# Sheet1.net
KiCad netlist of a schematic drawn in Altium Designer
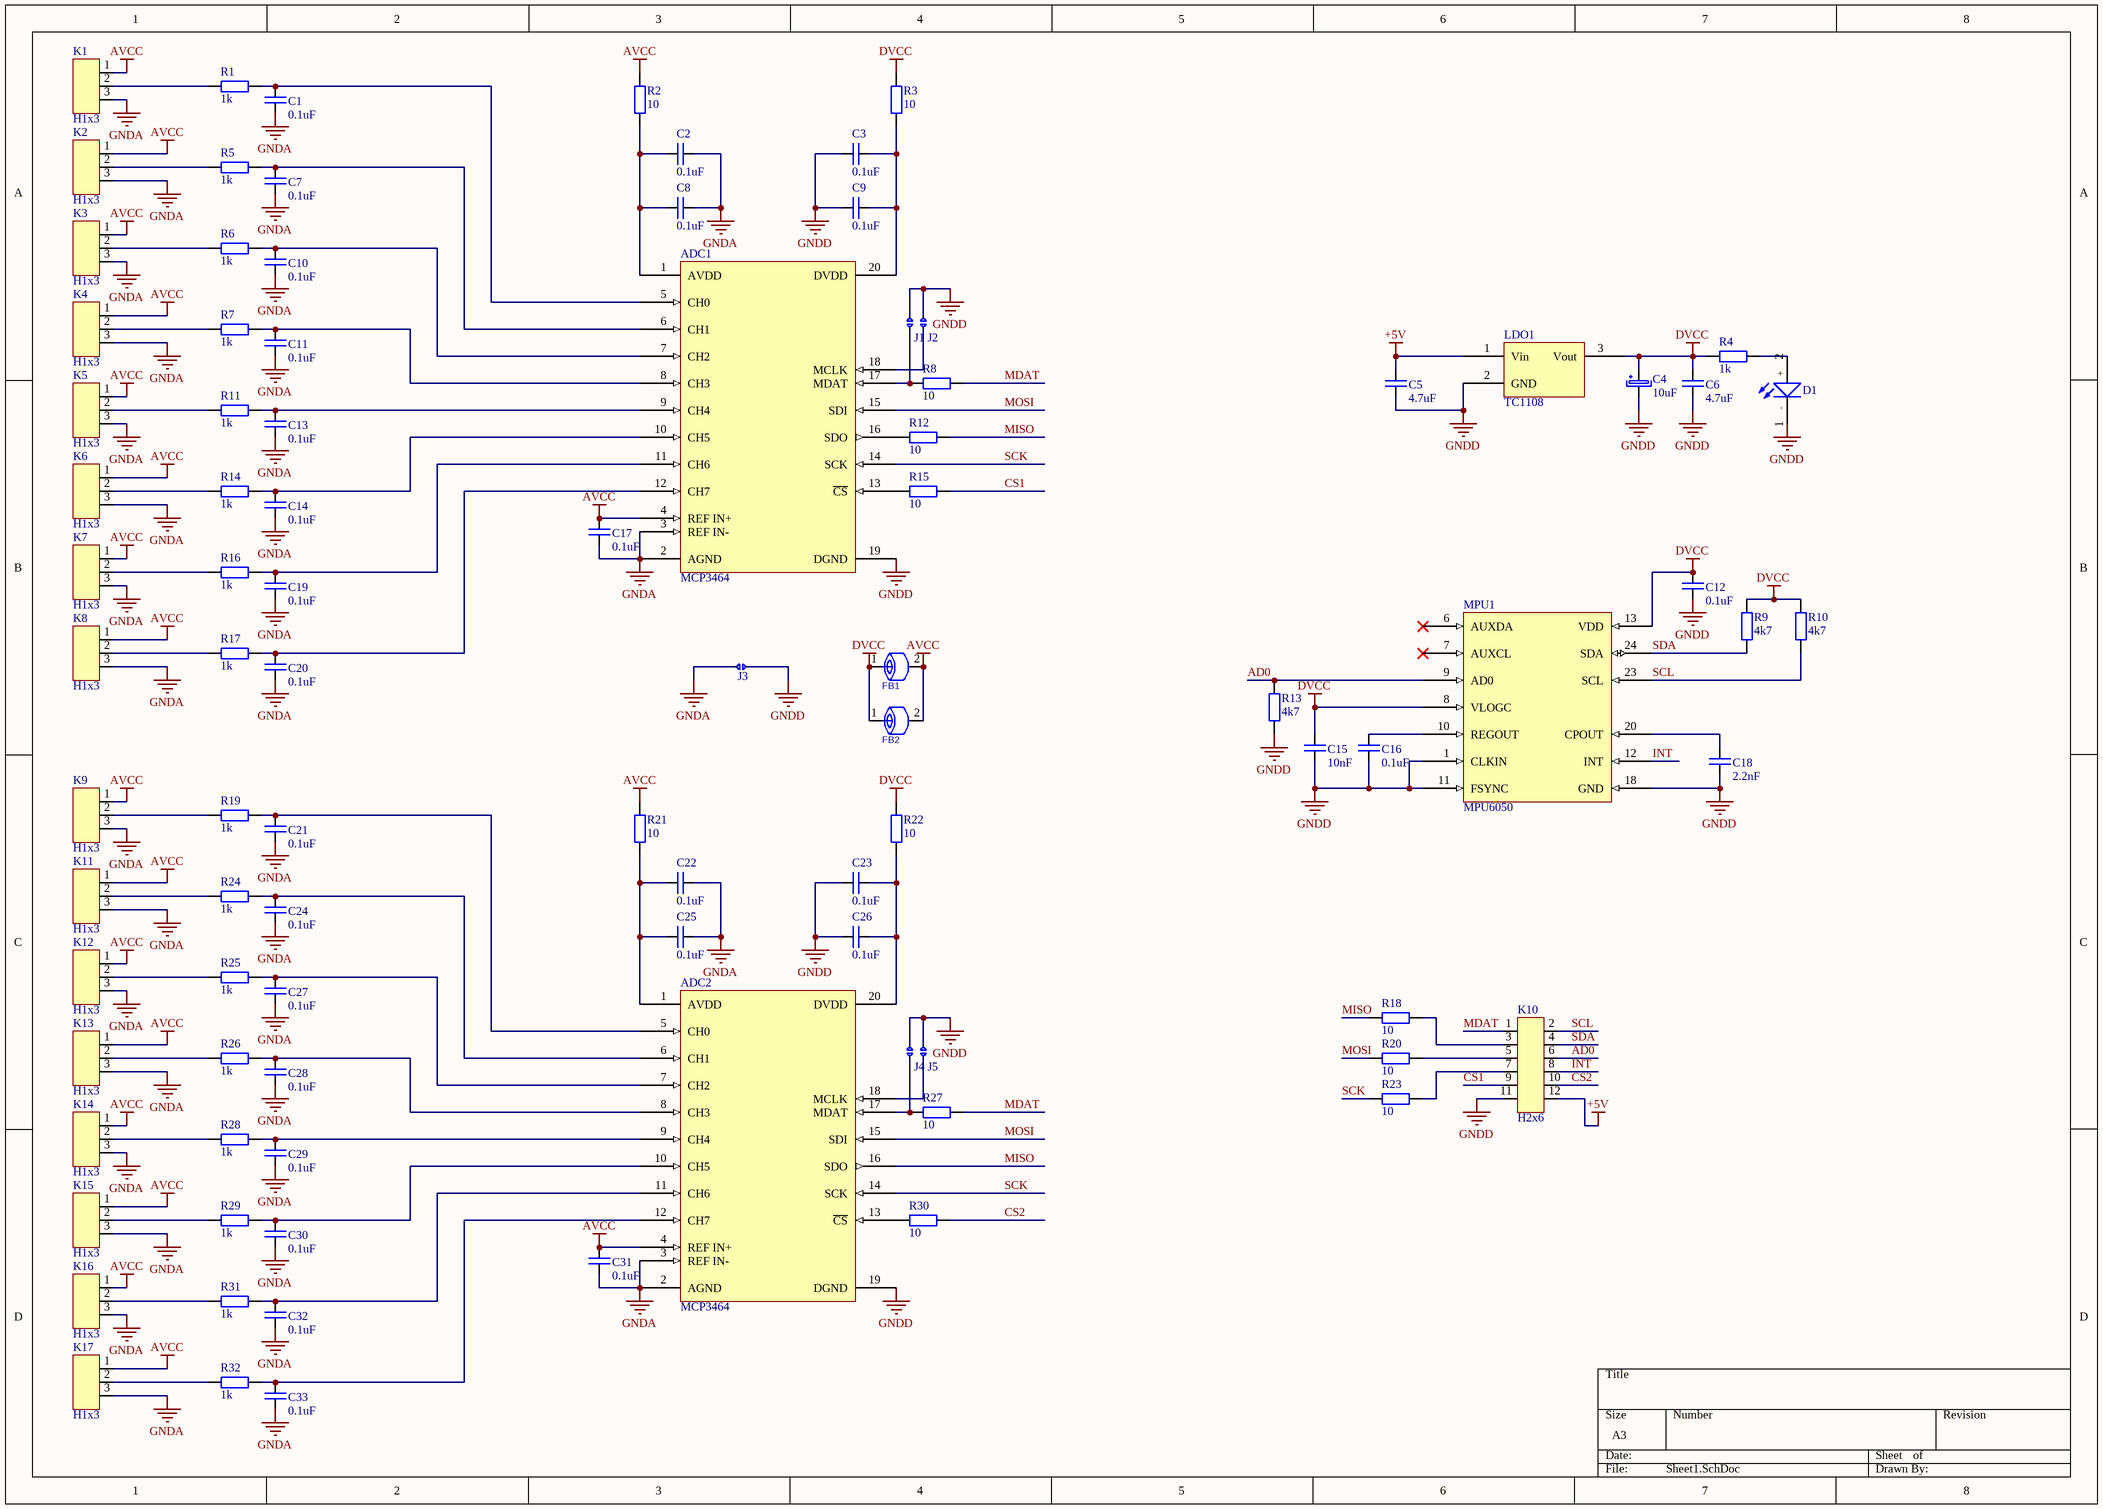
[diagram p0: Sheet1.SchDoc]

(export (version "E")
  (design (tool "Eeschema 10.0.6"))
  (components
    (comp (ref "ADC1")
      (value "MCP3464")
      (footprint "TSOP65P640X120-20N ADC")
      (libsource (lib "IntLibARMA") (part "MCP3464"))
    )
    (comp (ref "ADC2")
      (value "MCP3464")
      (footprint "TSOP65P640X120-20N ADC")
      (libsource (lib "IntLibARMA") (part "MCP3464"))
    )
    (comp (ref "C1")
      (value "0.1uF")
      (footprint "C1608_0603I_M")
      (description "Capacitor")
      (libsource (lib "General") (part "C"))
    )
    (comp (ref "C2")
      (value "0.1uF")
      (footprint "C1608_0603I_M")
      (description "Capacitor")
      (libsource (lib "General") (part "C"))
    )
    (comp (ref "C3")
      (value "0.1uF")
      (footprint "C1608_0603I_M")
      (description "Capacitor")
      (libsource (lib "General") (part "C"))
    )
    (comp (ref "C4")
      (value "10uF")
      (footprint "C Tantal A")
      (description "Capacitor Polarized")
      (libsource (lib "General") (part "C+"))
    )
    (comp (ref "C5")
      (value "4.7uF")
      (footprint "C1608_0603I_M")
      (description "Capacitor")
      (libsource (lib "General") (part "C"))
    )
    (comp (ref "C6")
      (value "4.7uF")
      (footprint "C1608_0603I_M")
      (description "Capacitor")
      (libsource (lib "General") (part "C"))
    )
    (comp (ref "C7")
      (value "0.1uF")
      (footprint "C1608_0603I_M")
      (description "Capacitor")
      (libsource (lib "General") (part "C"))
    )
    (comp (ref "C8")
      (value "0.1uF")
      (footprint "C1608_0603I_M")
      (description "Capacitor")
      (libsource (lib "General") (part "C"))
    )
    (comp (ref "C9")
      (value "0.1uF")
      (footprint "C1608_0603I_M")
      (description "Capacitor")
      (libsource (lib "General") (part "C"))
    )
    (comp (ref "C10")
      (value "0.1uF")
      (footprint "C1608_0603I_M")
      (description "Capacitor")
      (libsource (lib "General") (part "C"))
    )
    (comp (ref "C11")
      (value "0.1uF")
      (footprint "C1608_0603I_M")
      (description "Capacitor")
      (libsource (lib "General") (part "C"))
    )
    (comp (ref "C12")
      (value "0.1uF")
      (footprint "C1608_0603I_M")
      (description "Capacitor")
      (libsource (lib "General") (part "C"))
    )
    (comp (ref "C13")
      (value "0.1uF")
      (footprint "C1608_0603I_M")
      (description "Capacitor")
      (libsource (lib "General") (part "C"))
    )
    (comp (ref "C14")
      (value "0.1uF")
      (footprint "C1608_0603I_M")
      (description "Capacitor")
      (libsource (lib "General") (part "C"))
    )
    (comp (ref "C15")
      (value "10nF")
      (footprint "C1608_0603I_M")
      (description "Capacitor")
      (libsource (lib "General") (part "C"))
    )
    (comp (ref "C16")
      (value "0.1uF")
      (footprint "C1608_0603I_M")
      (description "Capacitor")
      (libsource (lib "General") (part "C"))
    )
    (comp (ref "C17")
      (value "0.1uF")
      (footprint "C1608_0603I_M")
      (description "Capacitor")
      (libsource (lib "General") (part "C"))
    )
    (comp (ref "C18")
      (value "2.2nF")
      (footprint "C1608_0603I_M")
      (description "Capacitor")
      (libsource (lib "General") (part "C"))
    )
    (comp (ref "C19")
      (value "0.1uF")
      (footprint "C1608_0603I_M")
      (description "Capacitor")
      (libsource (lib "General") (part "C"))
    )
    (comp (ref "C20")
      (value "0.1uF")
      (footprint "C1608_0603I_M")
      (description "Capacitor")
      (libsource (lib "General") (part "C"))
    )
    (comp (ref "C21")
      (value "0.1uF")
      (footprint "C1608_0603I_M")
      (description "Capacitor")
      (libsource (lib "General") (part "C"))
    )
    (comp (ref "C22")
      (value "0.1uF")
      (footprint "C1608_0603I_M")
      (description "Capacitor")
      (libsource (lib "General") (part "C"))
    )
    (comp (ref "C23")
      (value "0.1uF")
      (footprint "C1608_0603I_M")
      (description "Capacitor")
      (libsource (lib "General") (part "C"))
    )
    (comp (ref "C24")
      (value "0.1uF")
      (footprint "C1608_0603I_M")
      (description "Capacitor")
      (libsource (lib "General") (part "C"))
    )
    (comp (ref "C25")
      (value "0.1uF")
      (footprint "C1608_0603I_M")
      (description "Capacitor")
      (libsource (lib "General") (part "C"))
    )
    (comp (ref "C26")
      (value "0.1uF")
      (footprint "C1608_0603I_M")
      (description "Capacitor")
      (libsource (lib "General") (part "C"))
    )
    (comp (ref "C27")
      (value "0.1uF")
      (footprint "C1608_0603I_M")
      (description "Capacitor")
      (libsource (lib "General") (part "C"))
    )
    (comp (ref "C28")
      (value "0.1uF")
      (footprint "C1608_0603I_M")
      (description "Capacitor")
      (libsource (lib "General") (part "C"))
    )
    (comp (ref "C29")
      (value "0.1uF")
      (footprint "C1608_0603I_M")
      (description "Capacitor")
      (libsource (lib "General") (part "C"))
    )
    (comp (ref "C30")
      (value "0.1uF")
      (footprint "C1608_0603I_M")
      (description "Capacitor")
      (libsource (lib "General") (part "C"))
    )
    (comp (ref "C31")
      (value "0.1uF")
      (footprint "C1608_0603I_M")
      (description "Capacitor")
      (libsource (lib "General") (part "C"))
    )
    (comp (ref "C32")
      (value "0.1uF")
      (footprint "C1608_0603I_M")
      (description "Capacitor")
      (libsource (lib "General") (part "C"))
    )
    (comp (ref "C33")
      (value "0.1uF")
      (footprint "C1608_0603I_M")
      (description "Capacitor")
      (libsource (lib "General") (part "C"))
    )
    (comp (ref "D1") (value "LED") (footprint "LED1608_0603I_M") (libsource (lib "General") (part "LED")))
    (comp (ref "FB1")
      (value "FERITTE BEAD")
      (footprint "R1608_0603I_M")
      (libsource (lib "General") (part "FERITTE BEAD"))
    )
    (comp (ref "FB2")
      (value "FERITTE BEAD")
      (footprint "R1608_0603I_M")
      (libsource (lib "General") (part "FERITTE BEAD"))
    )
    (comp (ref "J1")
      (value "JMP_mini")
      (footprint "solderJumper")
      (libsource (lib "Kon_Tipk") (part "JMP_mini"))
    )
    (comp (ref "J2")
      (value "JMP_mini")
      (footprint "solderJumper")
      (libsource (lib "Kon_Tipk") (part "JMP_mini"))
    )
    (comp (ref "J3")
      (value "JMP_mini")
      (footprint "solderJumper")
      (libsource (lib "Kon_Tipk") (part "JMP_mini"))
    )
    (comp (ref "J4")
      (value "JMP_mini")
      (footprint "solderJumper")
      (libsource (lib "Kon_Tipk") (part "JMP_mini"))
    )
    (comp (ref "J5")
      (value "JMP_mini")
      (footprint "solderJumper")
      (libsource (lib "Kon_Tipk") (part "JMP_mini"))
    )
    (comp (ref "K1")
      (value "H1x3")
      (footprint "H1x3")
      (description "Header 1x3 (male)")
      (libsource (lib "Kon_Tipk") (part "H1x3"))
    )
    (comp (ref "K2")
      (value "H1x3")
      (footprint "H1x3")
      (description "Header 1x3 (male)")
      (libsource (lib "Kon_Tipk") (part "H1x3"))
    )
    (comp (ref "K3")
      (value "H1x3")
      (footprint "H1x3")
      (description "Header 1x3 (male)")
      (libsource (lib "Kon_Tipk") (part "H1x3"))
    )
    (comp (ref "K4")
      (value "H1x3")
      (footprint "H1x3")
      (description "Header 1x3 (male)")
      (libsource (lib "Kon_Tipk") (part "H1x3"))
    )
    (comp (ref "K5")
      (value "H1x3")
      (footprint "H1x3")
      (description "Header 1x3 (male)")
      (libsource (lib "Kon_Tipk") (part "H1x3"))
    )
    (comp (ref "K6")
      (value "H1x3")
      (footprint "H1x3")
      (description "Header 1x3 (male)")
      (libsource (lib "Kon_Tipk") (part "H1x3"))
    )
    (comp (ref "K7")
      (value "H1x3")
      (footprint "H1x3")
      (description "Header 1x3 (male)")
      (libsource (lib "Kon_Tipk") (part "H1x3"))
    )
    (comp (ref "K8")
      (value "H1x3")
      (footprint "H1x3")
      (description "Header 1x3 (male)")
      (libsource (lib "Kon_Tipk") (part "H1x3"))
    )
    (comp (ref "K9")
      (value "H1x3")
      (footprint "H1x3")
      (description "Header 1x3 (male)")
      (libsource (lib "Kon_Tipk") (part "H1x3"))
    )
    (comp (ref "K10")
      (value "H2x6")
      (footprint "H2x6")
      (description "Header 2x5 (male)")
      (libsource (lib "Kon_Tipk") (part "H2x6"))
    )
    (comp (ref "K11")
      (value "H1x3")
      (footprint "H1x3")
      (description "Header 1x3 (male)")
      (libsource (lib "Kon_Tipk") (part "H1x3"))
    )
    (comp (ref "K12")
      (value "H1x3")
      (footprint "H1x3")
      (description "Header 1x3 (male)")
      (libsource (lib "Kon_Tipk") (part "H1x3"))
    )
    (comp (ref "K13")
      (value "H1x3")
      (footprint "H1x3")
      (description "Header 1x3 (male)")
      (libsource (lib "Kon_Tipk") (part "H1x3"))
    )
    (comp (ref "K14")
      (value "H1x3")
      (footprint "H1x3")
      (description "Header 1x3 (male)")
      (libsource (lib "Kon_Tipk") (part "H1x3"))
    )
    (comp (ref "K15")
      (value "H1x3")
      (footprint "H1x3")
      (description "Header 1x3 (male)")
      (libsource (lib "Kon_Tipk") (part "H1x3"))
    )
    (comp (ref "K16")
      (value "H1x3")
      (footprint "H1x3")
      (description "Header 1x3 (male)")
      (libsource (lib "Kon_Tipk") (part "H1x3"))
    )
    (comp (ref "K17")
      (value "H1x3")
      (footprint "H1x3")
      (description "Header 1x3 (male)")
      (libsource (lib "Kon_Tipk") (part "H1x3"))
    )
    (comp (ref "LDO1")
      (value "TC1108")
      (footprint "SOT230P700X180-4N 3V3 LDO")
      (libsource (lib "IntLibARMA") (part "TC1108"))
    )
    (comp (ref "MPU1")
      (value "MPU6050")
      (footprint "QFN50P400X400X95_HS-25N")
      (libsource (lib "IntLibARMA") (part "MPU6050"))
    )
    (comp (ref "R1")
      (value "1k")
      (footprint "R1608_0603I_M")
      (description "R")
      (libsource (lib "General") (part "R"))
    )
    (comp (ref "R2")
      (value "10")
      (footprint "R1608_0603I_M")
      (description "R")
      (libsource (lib "General") (part "R"))
    )
    (comp (ref "R3")
      (value "10")
      (footprint "R1608_0603I_M")
      (description "R")
      (libsource (lib "General") (part "R"))
    )
    (comp (ref "R4")
      (value "1k")
      (footprint "R1608_0603I_M")
      (description "R")
      (libsource (lib "General") (part "R"))
    )
    (comp (ref "R5")
      (value "1k")
      (footprint "R1608_0603I_M")
      (description "R")
      (libsource (lib "General") (part "R"))
    )
    (comp (ref "R6")
      (value "1k")
      (footprint "R1608_0603I_M")
      (description "R")
      (libsource (lib "General") (part "R"))
    )
    (comp (ref "R7")
      (value "1k")
      (footprint "R1608_0603I_M")
      (description "R")
      (libsource (lib "General") (part "R"))
    )
    (comp (ref "R8")
      (value "10")
      (footprint "R1608_0603I_M")
      (description "R")
      (libsource (lib "General") (part "R"))
    )
    (comp (ref "R9")
      (value "4k7")
      (footprint "R1608_0603I_M")
      (description "R")
      (libsource (lib "General") (part "R"))
    )
    (comp (ref "R10")
      (value "4k7")
      (footprint "R1608_0603I_M")
      (description "R")
      (libsource (lib "General") (part "R"))
    )
    (comp (ref "R11")
      (value "1k")
      (footprint "R1608_0603I_M")
      (description "R")
      (libsource (lib "General") (part "R"))
    )
    (comp (ref "R12")
      (value "10")
      (footprint "R1608_0603I_M")
      (description "R")
      (libsource (lib "General") (part "R"))
    )
    (comp (ref "R13")
      (value "4k7")
      (footprint "R1608_0603I_M")
      (description "R")
      (libsource (lib "General") (part "R"))
    )
    (comp (ref "R14")
      (value "1k")
      (footprint "R1608_0603I_M")
      (description "R")
      (libsource (lib "General") (part "R"))
    )
    (comp (ref "R15")
      (value "10")
      (footprint "R1608_0603I_M")
      (description "R")
      (libsource (lib "General") (part "R"))
    )
    (comp (ref "R16")
      (value "1k")
      (footprint "R1608_0603I_M")
      (description "R")
      (libsource (lib "General") (part "R"))
    )
    (comp (ref "R17")
      (value "1k")
      (footprint "R1608_0603I_M")
      (description "R")
      (libsource (lib "General") (part "R"))
    )
    (comp (ref "R18")
      (value "10")
      (footprint "R1608_0603I_M")
      (description "R")
      (libsource (lib "General") (part "R"))
    )
    (comp (ref "R19")
      (value "1k")
      (footprint "R1608_0603I_M")
      (description "R")
      (libsource (lib "General") (part "R"))
    )
    (comp (ref "R20")
      (value "10")
      (footprint "R1608_0603I_M")
      (description "R")
      (libsource (lib "General") (part "R"))
    )
    (comp (ref "R21")
      (value "10")
      (footprint "R1608_0603I_M")
      (description "R")
      (libsource (lib "General") (part "R"))
    )
    (comp (ref "R22")
      (value "10")
      (footprint "R1608_0603I_M")
      (description "R")
      (libsource (lib "General") (part "R"))
    )
    (comp (ref "R23")
      (value "10")
      (footprint "R1608_0603I_M")
      (description "R")
      (libsource (lib "General") (part "R"))
    )
    (comp (ref "R24")
      (value "1k")
      (footprint "R1608_0603I_M")
      (description "R")
      (libsource (lib "General") (part "R"))
    )
    (comp (ref "R25")
      (value "1k")
      (footprint "R1608_0603I_M")
      (description "R")
      (libsource (lib "General") (part "R"))
    )
    (comp (ref "R26")
      (value "1k")
      (footprint "R1608_0603I_M")
      (description "R")
      (libsource (lib "General") (part "R"))
    )
    (comp (ref "R27")
      (value "10")
      (footprint "R1608_0603I_M")
      (description "R")
      (libsource (lib "General") (part "R"))
    )
    (comp (ref "R28")
      (value "1k")
      (footprint "R1608_0603I_M")
      (description "R")
      (libsource (lib "General") (part "R"))
    )
    (comp (ref "R29")
      (value "1k")
      (footprint "R1608_0603I_M")
      (description "R")
      (libsource (lib "General") (part "R"))
    )
    (comp (ref "R30")
      (value "10")
      (footprint "R1608_0603I_M")
      (description "R")
      (libsource (lib "General") (part "R"))
    )
    (comp (ref "R31")
      (value "1k")
      (footprint "R1608_0603I_M")
      (description "R")
      (libsource (lib "General") (part "R"))
    )
    (comp (ref "R32")
      (value "1k")
      (footprint "R1608_0603I_M")
      (description "R")
      (libsource (lib "General") (part "R"))
    )
  )
  (nets
    (net (code "1") (name "+5V") (class "Default")
      (node (ref "C5") (pin "1") (pinfunction "1_1") (pintype "passive"))
      (node (ref "K10") (pin "12") (pinfunction "12_12") (pintype "passive"))
      (node (ref "LDO1") (pin "1") (pinfunction "Vin_1") (pintype "power_in"))
    )
    (net (code "2") (name "/AD0") (class "Default")
      (node (ref "K10") (pin "6") (pinfunction "6_6") (pintype "passive"))
      (node (ref "MPU1") (pin "9") (pinfunction "AD0_9") (pintype "input"))
      (node (ref "R13") (pin "1") (pintype "passive"))
    )
    (net (code "3") (name "/CS1") (class "Default")
      (node (ref "K10") (pin "9") (pinfunction "9_9") (pintype "passive"))
      (node (ref "R15") (pin "2") (pintype "passive"))
    )
    (net (code "4") (name "/CS2") (class "Default")
      (node (ref "K10") (pin "10") (pinfunction "10_10") (pintype "passive"))
      (node (ref "R30") (pin "2") (pintype "passive"))
    )
    (net (code "5") (name "/INT") (class "Default")
      (node (ref "K10") (pin "8") (pinfunction "8_8") (pintype "passive"))
      (node (ref "MPU1") (pin "12") (pinfunction "INT_12") (pintype "input"))
    )
    (net (code "6") (name "/MDAT") (class "Default")
      (node (ref "K10") (pin "1") (pinfunction "1_1") (pintype "passive"))
      (node (ref "R27") (pin "2") (pintype "passive"))
      (node (ref "R8") (pin "2") (pintype "passive"))
    )
    (net (code "7") (name "/MISO") (class "Default")
      (node (ref "ADC2") (pin "16") (pinfunction "SDO_16") (pintype "output"))
      (node (ref "R12") (pin "2") (pintype "passive"))
      (node (ref "R18") (pin "1") (pintype "passive"))
    )
    (net (code "8") (name "/MOSI") (class "Default")
      (node (ref "ADC1") (pin "15") (pinfunction "SDI_15") (pintype "input"))
      (node (ref "ADC2") (pin "15") (pinfunction "SDI_15") (pintype "input"))
      (node (ref "R20") (pin "1") (pintype "passive"))
    )
    (net (code "9") (name "/SCK") (class "Default")
      (node (ref "ADC1") (pin "14") (pinfunction "SCK_14") (pintype "input"))
      (node (ref "ADC2") (pin "14") (pinfunction "SCK_14") (pintype "input"))
      (node (ref "R23") (pin "1") (pintype "passive"))
    )
    (net (code "10") (name "/SCL") (class "Default")
      (node (ref "K10") (pin "2") (pinfunction "2_2") (pintype "passive"))
      (node (ref "MPU1") (pin "23") (pinfunction "SCL_23") (pintype "input"))
      (node (ref "R10") (pin "2") (pintype "passive"))
    )
    (net (code "11") (name "/SDA") (class "Default")
      (node (ref "K10") (pin "4") (pinfunction "4_4") (pintype "passive"))
      (node (ref "MPU1") (pin "24") (pinfunction "SDA_24") (pintype "bidirectional"))
      (node (ref "R9") (pin "1") (pintype "passive"))
    )
    (net (code "12") (name "AVCC") (class "Default")
      (node (ref "ADC1") (pin "4") (pinfunction "REF_IN+_4") (pintype "input"))
      (node (ref "ADC2") (pin "4") (pinfunction "REF_IN+_4") (pintype "input"))
      (node (ref "C17") (pin "2") (pinfunction "2_2") (pintype "passive"))
      (node (ref "C31") (pin "2") (pinfunction "2_2") (pintype "passive"))
      (node (ref "FB1") (pin "2") (pintype "passive"))
      (node (ref "FB2") (pin "2") (pintype "passive"))
      (node (ref "K1") (pin "1") (pinfunction "1_1") (pintype "passive"))
      (node (ref "K11") (pin "1") (pinfunction "1_1") (pintype "passive"))
      (node (ref "K12") (pin "1") (pinfunction "1_1") (pintype "passive"))
      (node (ref "K13") (pin "1") (pinfunction "1_1") (pintype "passive"))
      (node (ref "K14") (pin "1") (pinfunction "1_1") (pintype "passive"))
      (node (ref "K15") (pin "1") (pinfunction "1_1") (pintype "passive"))
      (node (ref "K16") (pin "1") (pinfunction "1_1") (pintype "passive"))
      (node (ref "K17") (pin "1") (pinfunction "1_1") (pintype "passive"))
      (node (ref "K2") (pin "1") (pinfunction "1_1") (pintype "passive"))
      (node (ref "K3") (pin "1") (pinfunction "1_1") (pintype "passive"))
      (node (ref "K4") (pin "1") (pinfunction "1_1") (pintype "passive"))
      (node (ref "K5") (pin "1") (pinfunction "1_1") (pintype "passive"))
      (node (ref "K6") (pin "1") (pinfunction "1_1") (pintype "passive"))
      (node (ref "K7") (pin "1") (pinfunction "1_1") (pintype "passive"))
      (node (ref "K8") (pin "1") (pinfunction "1_1") (pintype "passive"))
      (node (ref "K9") (pin "1") (pinfunction "1_1") (pintype "passive"))
      (node (ref "R2") (pin "1") (pintype "passive"))
      (node (ref "R21") (pin "1") (pintype "passive"))
    )
    (net (code "13") (name "DVCC") (class "Default")
      (node (ref "C12") (pin "2") (pinfunction "2_2") (pintype "passive"))
      (node (ref "C15") (pin "1") (pinfunction "1_1") (pintype "passive"))
      (node (ref "C4") (pin "1") (pinfunction "1_1") (pintype "passive"))
      (node (ref "C6") (pin "1") (pinfunction "1_1") (pintype "passive"))
      (node (ref "FB1") (pin "1") (pintype "passive"))
      (node (ref "FB2") (pin "1") (pintype "passive"))
      (node (ref "LDO1") (pin "3") (pinfunction "Vout_3") (pintype "power_in"))
      (node (ref "MPU1") (pin "13") (pinfunction "VDD_13") (pintype "input"))
      (node (ref "MPU1") (pin "8") (pinfunction "VLOGC_8") (pintype "input"))
      (node (ref "R10") (pin "1") (pintype "passive"))
      (node (ref "R22") (pin "1") (pintype "passive"))
      (node (ref "R3") (pin "1") (pintype "passive"))
      (node (ref "R4") (pin "1") (pintype "passive"))
      (node (ref "R9") (pin "2") (pintype "passive"))
    )
    (net (code "14") (name "GNDA") (class "Default")
      (node (ref "ADC1") (pin "2") (pinfunction "AGND_2") (pintype "power_in"))
      (node (ref "ADC1") (pin "3") (pinfunction "REF_IN-_3") (pintype "input"))
      (node (ref "ADC2") (pin "2") (pinfunction "AGND_2") (pintype "power_in"))
      (node (ref "ADC2") (pin "3") (pinfunction "REF_IN-_3") (pintype "input"))
      (node (ref "C1") (pin "1") (pinfunction "1_1") (pintype "passive"))
      (node (ref "C10") (pin "1") (pinfunction "1_1") (pintype "passive"))
      (node (ref "C11") (pin "1") (pinfunction "1_1") (pintype "passive"))
      (node (ref "C13") (pin "1") (pinfunction "1_1") (pintype "passive"))
      (node (ref "C14") (pin "1") (pinfunction "1_1") (pintype "passive"))
      (node (ref "C17") (pin "1") (pinfunction "1_1") (pintype "passive"))
      (node (ref "C19") (pin "1") (pinfunction "1_1") (pintype "passive"))
      (node (ref "C2") (pin "2") (pinfunction "2_2") (pintype "passive"))
      (node (ref "C20") (pin "1") (pinfunction "1_1") (pintype "passive"))
      (node (ref "C21") (pin "1") (pinfunction "1_1") (pintype "passive"))
      (node (ref "C22") (pin "2") (pinfunction "2_2") (pintype "passive"))
      (node (ref "C24") (pin "1") (pinfunction "1_1") (pintype "passive"))
      (node (ref "C25") (pin "2") (pinfunction "2_2") (pintype "passive"))
      (node (ref "C27") (pin "1") (pinfunction "1_1") (pintype "passive"))
      (node (ref "C28") (pin "1") (pinfunction "1_1") (pintype "passive"))
      (node (ref "C29") (pin "1") (pinfunction "1_1") (pintype "passive"))
      (node (ref "C30") (pin "1") (pinfunction "1_1") (pintype "passive"))
      (node (ref "C31") (pin "1") (pinfunction "1_1") (pintype "passive"))
      (node (ref "C32") (pin "1") (pinfunction "1_1") (pintype "passive"))
      (node (ref "C33") (pin "1") (pinfunction "1_1") (pintype "passive"))
      (node (ref "C7") (pin "1") (pinfunction "1_1") (pintype "passive"))
      (node (ref "C8") (pin "2") (pinfunction "2_2") (pintype "passive"))
      (node (ref "J3") (pin "2") (pinfunction "2_2") (pintype "passive"))
      (node (ref "K1") (pin "3") (pinfunction "3_3") (pintype "passive"))
      (node (ref "K11") (pin "3") (pinfunction "3_3") (pintype "passive"))
      (node (ref "K12") (pin "3") (pinfunction "3_3") (pintype "passive"))
      (node (ref "K13") (pin "3") (pinfunction "3_3") (pintype "passive"))
      (node (ref "K14") (pin "3") (pinfunction "3_3") (pintype "passive"))
      (node (ref "K15") (pin "3") (pinfunction "3_3") (pintype "passive"))
      (node (ref "K16") (pin "3") (pinfunction "3_3") (pintype "passive"))
      (node (ref "K17") (pin "3") (pinfunction "3_3") (pintype "passive"))
      (node (ref "K2") (pin "3") (pinfunction "3_3") (pintype "passive"))
      (node (ref "K3") (pin "3") (pinfunction "3_3") (pintype "passive"))
      (node (ref "K4") (pin "3") (pinfunction "3_3") (pintype "passive"))
      (node (ref "K5") (pin "3") (pinfunction "3_3") (pintype "passive"))
      (node (ref "K6") (pin "3") (pinfunction "3_3") (pintype "passive"))
      (node (ref "K7") (pin "3") (pinfunction "3_3") (pintype "passive"))
      (node (ref "K8") (pin "3") (pinfunction "3_3") (pintype "passive"))
      (node (ref "K9") (pin "3") (pinfunction "3_3") (pintype "passive"))
    )
    (net (code "15") (name "GNDD") (class "Default")
      (node (ref "ADC1") (pin "19") (pinfunction "DGND_19") (pintype "power_in"))
      (node (ref "ADC2") (pin "19") (pinfunction "DGND_19") (pintype "power_in"))
      (node (ref "C12") (pin "1") (pinfunction "1_1") (pintype "passive"))
      (node (ref "C15") (pin "2") (pinfunction "2_2") (pintype "passive"))
      (node (ref "C16") (pin "1") (pinfunction "1_1") (pintype "passive"))
      (node (ref "C18") (pin "2") (pinfunction "2_2") (pintype "passive"))
      (node (ref "C23") (pin "1") (pinfunction "1_1") (pintype "passive"))
      (node (ref "C26") (pin "1") (pinfunction "1_1") (pintype "passive"))
      (node (ref "C3") (pin "1") (pinfunction "1_1") (pintype "passive"))
      (node (ref "C4") (pin "2") (pinfunction "2_2") (pintype "passive"))
      (node (ref "C5") (pin "2") (pinfunction "2_2") (pintype "passive"))
      (node (ref "C6") (pin "2") (pinfunction "2_2") (pintype "passive"))
      (node (ref "C9") (pin "1") (pinfunction "1_1") (pintype "passive"))
      (node (ref "D1") (pin "1") (pinfunction "-_1") (pintype "passive"))
      (node (ref "J1") (pin "2") (pinfunction "2_2") (pintype "passive"))
      (node (ref "J2") (pin "2") (pinfunction "2_2") (pintype "passive"))
      (node (ref "J3") (pin "1") (pinfunction "1_1") (pintype "passive"))
      (node (ref "J4") (pin "2") (pinfunction "2_2") (pintype "passive"))
      (node (ref "J5") (pin "2") (pinfunction "2_2") (pintype "passive"))
      (node (ref "K10") (pin "11") (pinfunction "11_11") (pintype "passive"))
      (node (ref "LDO1") (pin "2") (pinfunction "GND_2") (pintype "power_in"))
      (node (ref "MPU1") (pin "1") (pinfunction "CLKIN_1") (pintype "input"))
      (node (ref "MPU1") (pin "11") (pinfunction "FSYNC_11") (pintype "input"))
      (node (ref "MPU1") (pin "18") (pinfunction "GND_18") (pintype "input"))
      (node (ref "R13") (pin "2") (pintype "passive"))
    )
    (net (code "16") (name "Net-(ADC1-AVDD)") (class "Default")
      (node (ref "ADC1") (pin "1") (pinfunction "AVDD_1") (pintype "power_in"))
      (node (ref "C2") (pin "1") (pinfunction "1_1") (pintype "passive"))
      (node (ref "C8") (pin "1") (pinfunction "1_1") (pintype "passive"))
      (node (ref "R2") (pin "2") (pintype "passive"))
    )
    (net (code "17") (name "Net-(ADC1-CH0)") (class "Default")
      (node (ref "ADC1") (pin "5") (pinfunction "CH0_5") (pintype "input"))
      (node (ref "C1") (pin "2") (pinfunction "2_2") (pintype "passive"))
      (node (ref "R1") (pin "2") (pintype "passive"))
    )
    (net (code "18") (name "Net-(ADC1-CH1)") (class "Default")
      (node (ref "ADC1") (pin "6") (pinfunction "CH1_6") (pintype "input"))
      (node (ref "C7") (pin "2") (pinfunction "2_2") (pintype "passive"))
      (node (ref "R5") (pin "2") (pintype "passive"))
    )
    (net (code "19") (name "Net-(ADC1-CH2)") (class "Default")
      (node (ref "ADC1") (pin "7") (pinfunction "CH2_7") (pintype "input"))
      (node (ref "C10") (pin "2") (pinfunction "2_2") (pintype "passive"))
      (node (ref "R6") (pin "2") (pintype "passive"))
    )
    (net (code "20") (name "Net-(ADC1-CH3)") (class "Default")
      (node (ref "ADC1") (pin "8") (pinfunction "CH3_8") (pintype "input"))
      (node (ref "C11") (pin "2") (pinfunction "2_2") (pintype "passive"))
      (node (ref "R7") (pin "2") (pintype "passive"))
    )
    (net (code "21") (name "Net-(ADC1-CH4)") (class "Default")
      (node (ref "ADC1") (pin "9") (pinfunction "CH4_9") (pintype "input"))
      (node (ref "C13") (pin "2") (pinfunction "2_2") (pintype "passive"))
      (node (ref "R11") (pin "2") (pintype "passive"))
    )
    (net (code "22") (name "Net-(ADC1-CH5)") (class "Default")
      (node (ref "ADC1") (pin "10") (pinfunction "CH5_10") (pintype "input"))
      (node (ref "C14") (pin "2") (pinfunction "2_2") (pintype "passive"))
      (node (ref "R14") (pin "2") (pintype "passive"))
    )
    (net (code "23") (name "Net-(ADC1-CH6)") (class "Default")
      (node (ref "ADC1") (pin "11") (pinfunction "CH6_11") (pintype "input"))
      (node (ref "C19") (pin "2") (pinfunction "2_2") (pintype "passive"))
      (node (ref "R16") (pin "2") (pintype "passive"))
    )
    (net (code "24") (name "Net-(ADC1-CH7)") (class "Default")
      (node (ref "ADC1") (pin "12") (pinfunction "CH7_12") (pintype "input"))
      (node (ref "C20") (pin "2") (pinfunction "2_2") (pintype "passive"))
      (node (ref "R17") (pin "2") (pintype "passive"))
    )
    (net (code "25") (name "Net-(ADC1-DVDD)") (class "Default")
      (node (ref "ADC1") (pin "20") (pinfunction "DVDD_20") (pintype "power_in"))
      (node (ref "C3") (pin "2") (pinfunction "2_2") (pintype "passive"))
      (node (ref "C9") (pin "2") (pinfunction "2_2") (pintype "passive"))
      (node (ref "R3") (pin "2") (pintype "passive"))
    )
    (net (code "26") (name "Net-(ADC1-MCLK)") (class "Default")
      (node (ref "ADC1") (pin "18") (pinfunction "MCLK_18") (pintype "input"))
      (node (ref "J2") (pin "1") (pinfunction "1_1") (pintype "passive"))
    )
    (net (code "27") (name "Net-(ADC1-MDAT)") (class "Default")
      (node (ref "ADC1") (pin "17") (pinfunction "MDAT_17") (pintype "input"))
      (node (ref "J1") (pin "1") (pinfunction "1_1") (pintype "passive"))
      (node (ref "R8") (pin "1") (pintype "passive"))
    )
    (net (code "28") (name "Net-(ADC1-SDO)") (class "Default")
      (node (ref "ADC1") (pin "16") (pinfunction "SDO_16") (pintype "output"))
      (node (ref "R12") (pin "1") (pintype "passive"))
    )
    (net (code "29") (name "Net-(ADC1-~{CS})") (class "Default")
      (node (ref "ADC1") (pin "13") (pinfunction "~{CS}_13") (pintype "input"))
      (node (ref "R15") (pin "1") (pintype "passive"))
    )
    (net (code "30") (name "Net-(ADC2-AVDD)") (class "Default")
      (node (ref "ADC2") (pin "1") (pinfunction "AVDD_1") (pintype "power_in"))
      (node (ref "C22") (pin "1") (pinfunction "1_1") (pintype "passive"))
      (node (ref "C25") (pin "1") (pinfunction "1_1") (pintype "passive"))
      (node (ref "R21") (pin "2") (pintype "passive"))
    )
    (net (code "31") (name "Net-(ADC2-CH0)") (class "Default")
      (node (ref "ADC2") (pin "5") (pinfunction "CH0_5") (pintype "input"))
      (node (ref "C21") (pin "2") (pinfunction "2_2") (pintype "passive"))
      (node (ref "R19") (pin "2") (pintype "passive"))
    )
    (net (code "32") (name "Net-(ADC2-CH1)") (class "Default")
      (node (ref "ADC2") (pin "6") (pinfunction "CH1_6") (pintype "input"))
      (node (ref "C24") (pin "2") (pinfunction "2_2") (pintype "passive"))
      (node (ref "R24") (pin "2") (pintype "passive"))
    )
    (net (code "33") (name "Net-(ADC2-CH2)") (class "Default")
      (node (ref "ADC2") (pin "7") (pinfunction "CH2_7") (pintype "input"))
      (node (ref "C27") (pin "2") (pinfunction "2_2") (pintype "passive"))
      (node (ref "R25") (pin "2") (pintype "passive"))
    )
    (net (code "34") (name "Net-(ADC2-CH3)") (class "Default")
      (node (ref "ADC2") (pin "8") (pinfunction "CH3_8") (pintype "input"))
      (node (ref "C28") (pin "2") (pinfunction "2_2") (pintype "passive"))
      (node (ref "R26") (pin "2") (pintype "passive"))
    )
    (net (code "35") (name "Net-(ADC2-CH4)") (class "Default")
      (node (ref "ADC2") (pin "9") (pinfunction "CH4_9") (pintype "input"))
      (node (ref "C29") (pin "2") (pinfunction "2_2") (pintype "passive"))
      (node (ref "R28") (pin "2") (pintype "passive"))
    )
    (net (code "36") (name "Net-(ADC2-CH5)") (class "Default")
      (node (ref "ADC2") (pin "10") (pinfunction "CH5_10") (pintype "input"))
      (node (ref "C30") (pin "2") (pinfunction "2_2") (pintype "passive"))
      (node (ref "R29") (pin "2") (pintype "passive"))
    )
    (net (code "37") (name "Net-(ADC2-CH6)") (class "Default")
      (node (ref "ADC2") (pin "11") (pinfunction "CH6_11") (pintype "input"))
      (node (ref "C32") (pin "2") (pinfunction "2_2") (pintype "passive"))
      (node (ref "R31") (pin "2") (pintype "passive"))
    )
    (net (code "38") (name "Net-(ADC2-CH7)") (class "Default")
      (node (ref "ADC2") (pin "12") (pinfunction "CH7_12") (pintype "input"))
      (node (ref "C33") (pin "2") (pinfunction "2_2") (pintype "passive"))
      (node (ref "R32") (pin "2") (pintype "passive"))
    )
    (net (code "39") (name "Net-(ADC2-DVDD)") (class "Default")
      (node (ref "ADC2") (pin "20") (pinfunction "DVDD_20") (pintype "power_in"))
      (node (ref "C23") (pin "2") (pinfunction "2_2") (pintype "passive"))
      (node (ref "C26") (pin "2") (pinfunction "2_2") (pintype "passive"))
      (node (ref "R22") (pin "2") (pintype "passive"))
    )
    (net (code "40") (name "Net-(ADC2-MCLK)") (class "Default")
      (node (ref "ADC2") (pin "18") (pinfunction "MCLK_18") (pintype "input"))
      (node (ref "J5") (pin "1") (pinfunction "1_1") (pintype "passive"))
    )
    (net (code "41") (name "Net-(ADC2-MDAT)") (class "Default")
      (node (ref "ADC2") (pin "17") (pinfunction "MDAT_17") (pintype "input"))
      (node (ref "J4") (pin "1") (pinfunction "1_1") (pintype "passive"))
      (node (ref "R27") (pin "1") (pintype "passive"))
    )
    (net (code "42") (name "Net-(ADC2-~{CS})") (class "Default")
      (node (ref "ADC2") (pin "13") (pinfunction "~{CS}_13") (pintype "input"))
      (node (ref "R30") (pin "1") (pintype "passive"))
    )
    (net (code "43") (name "Net-(D1-+)") (class "Default")
      (node (ref "D1") (pin "2") (pinfunction "+_2") (pintype "passive"))
      (node (ref "R4") (pin "2") (pintype "passive"))
    )
    (net (code "44") (name "Net-(K1-Pad2)") (class "Default")
      (node (ref "K1") (pin "2") (pinfunction "2_2") (pintype "passive"))
      (node (ref "R1") (pin "1") (pintype "passive"))
    )
    (net (code "45") (name "Net-(K2-Pad2)") (class "Default")
      (node (ref "K2") (pin "2") (pinfunction "2_2") (pintype "passive"))
      (node (ref "R5") (pin "1") (pintype "passive"))
    )
    (net (code "46") (name "Net-(K3-Pad2)") (class "Default")
      (node (ref "K3") (pin "2") (pinfunction "2_2") (pintype "passive"))
      (node (ref "R6") (pin "1") (pintype "passive"))
    )
    (net (code "47") (name "Net-(K4-Pad2)") (class "Default")
      (node (ref "K4") (pin "2") (pinfunction "2_2") (pintype "passive"))
      (node (ref "R7") (pin "1") (pintype "passive"))
    )
    (net (code "48") (name "Net-(K5-Pad2)") (class "Default")
      (node (ref "K5") (pin "2") (pinfunction "2_2") (pintype "passive"))
      (node (ref "R11") (pin "1") (pintype "passive"))
    )
    (net (code "49") (name "Net-(K6-Pad2)") (class "Default")
      (node (ref "K6") (pin "2") (pinfunction "2_2") (pintype "passive"))
      (node (ref "R14") (pin "1") (pintype "passive"))
    )
    (net (code "50") (name "Net-(K7-Pad2)") (class "Default")
      (node (ref "K7") (pin "2") (pinfunction "2_2") (pintype "passive"))
      (node (ref "R16") (pin "1") (pintype "passive"))
    )
    (net (code "51") (name "Net-(K8-Pad2)") (class "Default")
      (node (ref "K8") (pin "2") (pinfunction "2_2") (pintype "passive"))
      (node (ref "R17") (pin "1") (pintype "passive"))
    )
    (net (code "52") (name "Net-(K9-Pad2)") (class "Default")
      (node (ref "K9") (pin "2") (pinfunction "2_2") (pintype "passive"))
      (node (ref "R19") (pin "1") (pintype "passive"))
    )
    (net (code "53") (name "Net-(K10-Pad3)") (class "Default")
      (node (ref "K10") (pin "3") (pinfunction "3_3") (pintype "passive"))
      (node (ref "R18") (pin "2") (pintype "passive"))
    )
    (net (code "54") (name "Net-(K10-Pad5)") (class "Default")
      (node (ref "K10") (pin "5") (pinfunction "5_5") (pintype "passive"))
      (node (ref "R20") (pin "2") (pintype "passive"))
    )
    (net (code "55") (name "Net-(K10-Pad7)") (class "Default")
      (node (ref "K10") (pin "7") (pinfunction "7_7") (pintype "passive"))
      (node (ref "R23") (pin "2") (pintype "passive"))
    )
    (net (code "56") (name "Net-(K11-Pad2)") (class "Default")
      (node (ref "K11") (pin "2") (pinfunction "2_2") (pintype "passive"))
      (node (ref "R24") (pin "1") (pintype "passive"))
    )
    (net (code "57") (name "Net-(K12-Pad2)") (class "Default")
      (node (ref "K12") (pin "2") (pinfunction "2_2") (pintype "passive"))
      (node (ref "R25") (pin "1") (pintype "passive"))
    )
    (net (code "58") (name "Net-(K13-Pad2)") (class "Default")
      (node (ref "K13") (pin "2") (pinfunction "2_2") (pintype "passive"))
      (node (ref "R26") (pin "1") (pintype "passive"))
    )
    (net (code "59") (name "Net-(K14-Pad2)") (class "Default")
      (node (ref "K14") (pin "2") (pinfunction "2_2") (pintype "passive"))
      (node (ref "R28") (pin "1") (pintype "passive"))
    )
    (net (code "60") (name "Net-(K15-Pad2)") (class "Default")
      (node (ref "K15") (pin "2") (pinfunction "2_2") (pintype "passive"))
      (node (ref "R29") (pin "1") (pintype "passive"))
    )
    (net (code "61") (name "Net-(K16-Pad2)") (class "Default")
      (node (ref "K16") (pin "2") (pinfunction "2_2") (pintype "passive"))
      (node (ref "R31") (pin "1") (pintype "passive"))
    )
    (net (code "62") (name "Net-(K17-Pad2)") (class "Default")
      (node (ref "K17") (pin "2") (pinfunction "2_2") (pintype "passive"))
      (node (ref "R32") (pin "1") (pintype "passive"))
    )
    (net (code "63") (name "Net-(MPU1-CPOUT)") (class "Default")
      (node (ref "C18") (pin "1") (pinfunction "1_1") (pintype "passive"))
      (node (ref "MPU1") (pin "20") (pinfunction "CPOUT_20") (pintype "input"))
    )
    (net (code "64") (name "Net-(MPU1-REGOUT)") (class "Default")
      (node (ref "C16") (pin "2") (pinfunction "2_2") (pintype "passive"))
      (node (ref "MPU1") (pin "10") (pinfunction "REGOUT_10") (pintype "input"))
    )
    (net (code "65") (name "unconnected-(MPU1-AUXCL-Pad7)") (class "Default")
      (node (ref "MPU1") (pin "7") (pinfunction "AUXCL_7") (pintype "input+no_connect"))
    )
    (net (code "66") (name "unconnected-(MPU1-AUXDA-Pad6)") (class "Default")
      (node (ref "MPU1") (pin "6") (pinfunction "AUXDA_6") (pintype "input+no_connect"))
    )
  )
)
